# DRV5032DULPGM.net
KiCad netlist of a schematic drawn in Altium Designer
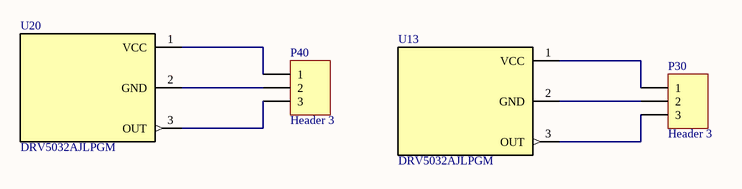
[diagram p0: DRV5032DULPGM.SchDoc]

(export (version "E")
  (design (tool "Eeschema 10.0.6"))
  (components
    (comp (ref "P30")
      (value "Header 3")
      (footprint "HDR1X3")
      (description "Header, 3-Pin")
      (fields (field (name "PUBLISHER") "Altium Limited"))
      (libsource (lib "Miscellaneous Connectors") (part "Header 3"))
    )
    (comp (ref "P40")
      (value "Header 3")
      (footprint "HDR1X3")
      (description "Header, 3-Pin")
      (fields (field (name "PUBLISHER") "Altium Limited"))
      (libsource (lib "Miscellaneous Connectors") (part "Header 3"))
    )
    (comp (ref "U13")
      (value "DRV5032AJLPGM")
      (footprint "SENSOR_DRV5055A2QLPGM")
      (description "Low power (5 Hz, <1ÂµA), low voltage (up to 5.5V) switch")
      (fields (field (name "MF") "Texas Instruments"))
      (libsource (lib "DRV5032DULPGM") (part "DRV5032AJLPGM"))
    )
    (comp (ref "U20")
      (value "DRV5032AJLPGM")
      (footprint "SENSOR_DRV5055A2QLPGM")
      (description "Low power (5 Hz, <1ÂµA), low voltage (up to 5.5V) switch")
      (fields (field (name "MF") "Texas Instruments"))
      (libsource (lib "DRV5032DULPGM") (part "DRV5032AJLPGM"))
    )
  )
  (nets
    (net (code "1") (name "Net-(U13-GND)") (class "Default")
      (node (ref "P30") (pin "2") (pinfunction "2_2") (pintype "passive"))
      (node (ref "U13") (pin "2") (pinfunction "GND_2") (pintype "power_in"))
    )
    (net (code "2") (name "Net-(U13-OUT)") (class "Default")
      (node (ref "P30") (pin "3") (pinfunction "3_3") (pintype "passive"))
      (node (ref "U13") (pin "3") (pinfunction "OUT_3") (pintype "output"))
    )
    (net (code "3") (name "Net-(U13-VCC)") (class "Default")
      (node (ref "P30") (pin "1") (pinfunction "1_1") (pintype "passive"))
      (node (ref "U13") (pin "1") (pinfunction "VCC_1") (pintype "power_in"))
    )
    (net (code "4") (name "Net-(U20-GND)") (class "Default")
      (node (ref "P40") (pin "2") (pinfunction "2_2") (pintype "passive"))
      (node (ref "U20") (pin "2") (pinfunction "GND_2") (pintype "power_in"))
    )
    (net (code "5") (name "Net-(U20-OUT)") (class "Default")
      (node (ref "P40") (pin "3") (pinfunction "3_3") (pintype "passive"))
      (node (ref "U20") (pin "3") (pinfunction "OUT_3") (pintype "output"))
    )
    (net (code "6") (name "Net-(U20-VCC)") (class "Default")
      (node (ref "P40") (pin "1") (pinfunction "1_1") (pintype "passive"))
      (node (ref "U20") (pin "1") (pinfunction "VCC_1") (pintype "power_in"))
    )
  )
)
